# Arduino_8FSR.net
KiCad netlist of a schematic drawn in EAGLE
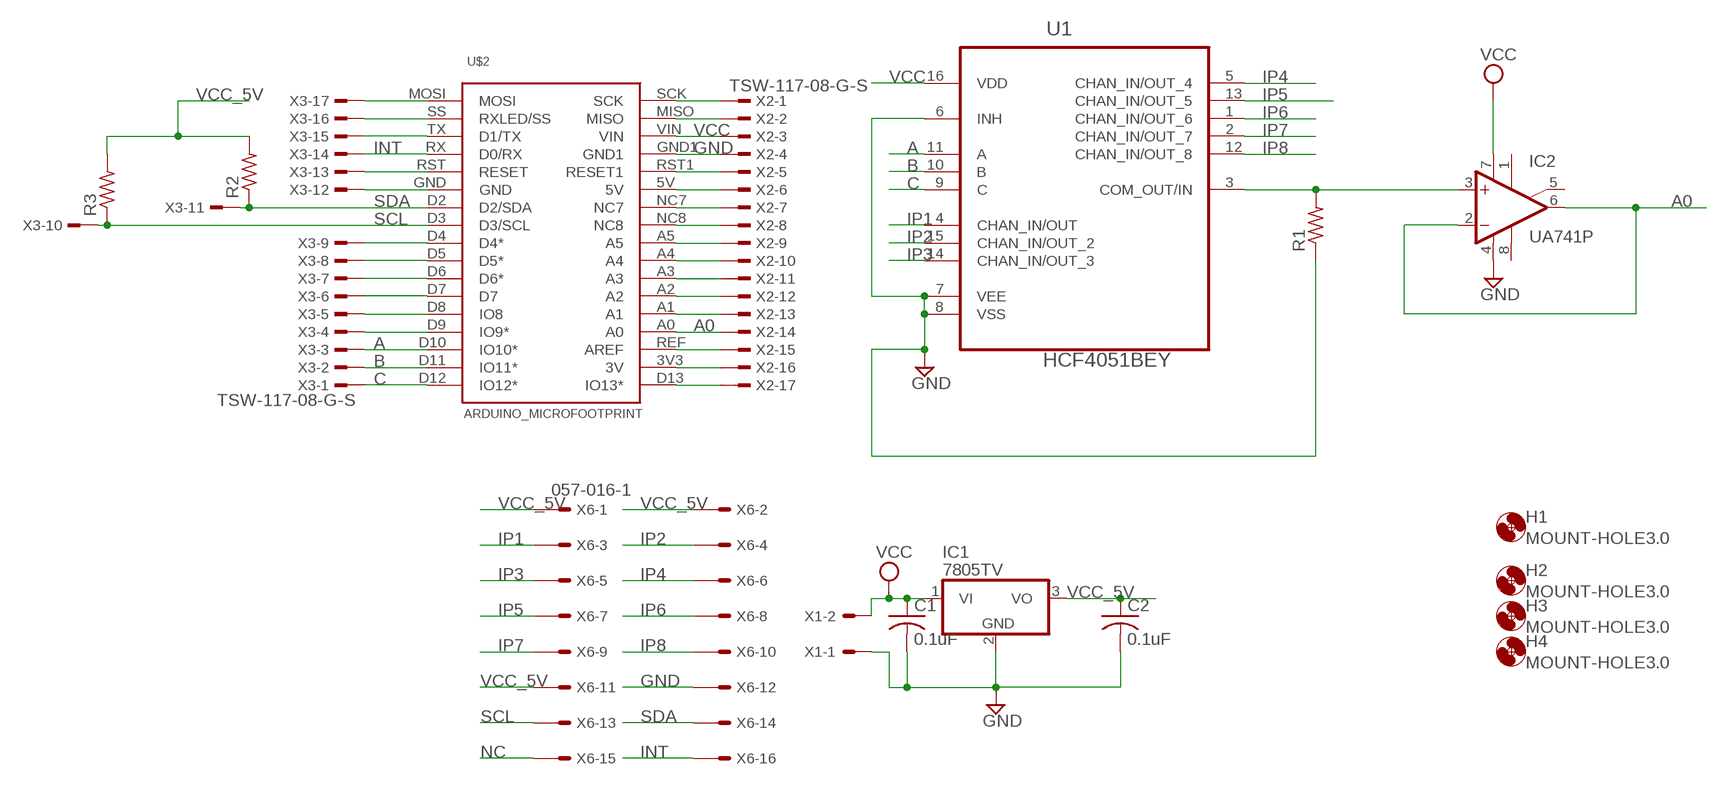
[diagram p0: schematic, sheet 1]

(export (version "E")
  (design (tool "Eeschema 10.0.6"))
  (components
    (comp (ref "C1")
      (value "0.1uF")
      (footprint "eagle-import:C025-024X044")
      (libsource (lib "eagle-import") (part "C-US025-024X044"))
    )
    (comp (ref "C2")
      (value "0.1uF")
      (footprint "eagle-import:C025-024X044")
      (libsource (lib "eagle-import") (part "C-US025-024X044"))
    )
    (comp (ref "H1")
      (value "MOUNT-HOLE3.0")
      (footprint "eagle-import:3,0")
      (libsource (lib "eagle-import") (part "MOUNT-HOLE3.0"))
    )
    (comp (ref "H2")
      (value "MOUNT-HOLE3.0")
      (footprint "eagle-import:3,0")
      (libsource (lib "eagle-import") (part "MOUNT-HOLE3.0"))
    )
    (comp (ref "H3")
      (value "MOUNT-HOLE3.0")
      (footprint "eagle-import:3,0")
      (libsource (lib "eagle-import") (part "MOUNT-HOLE3.0"))
    )
    (comp (ref "H4")
      (value "MOUNT-HOLE3.0")
      (footprint "eagle-import:3,0")
      (libsource (lib "eagle-import") (part "MOUNT-HOLE3.0"))
    )
    (comp (ref "IC1")
      (value "7805TV")
      (footprint "eagle-import:TO220V")
      (libsource (lib "eagle-import") (part "78TV05"))
    )
    (comp (ref "IC2")
      (value "UA741P")
      (footprint "eagle-import:DIL08")
      (libsource (lib "eagle-import") (part "741PUA"))
    )
    (comp (ref "R1")
      (value "R-US_0204/7")
      (footprint "eagle-import:0204_7")
      (libsource (lib "eagle-import") (part "R-US_0204/7"))
    )
    (comp (ref "R2")
      (value "R-US_0204/7")
      (footprint "eagle-import:0204_7")
      (libsource (lib "eagle-import") (part "R-US_0204/7"))
    )
    (comp (ref "R3")
      (value "R-US_0204/7")
      (footprint "eagle-import:0204_7")
      (libsource (lib "eagle-import") (part "R-US_0204/7"))
    )
    (comp (ref "U$2")
      (value "ARDUINO_MICROFOOTPRINT")
      (footprint "eagle-import:ARDUINO-MICRO")
      (libsource (lib "eagle-import") (part "ARDUINO_MICROFOOTPRINT"))
    )
    (comp (ref "U1")
      (value "HCF4051BEY")
      (footprint "eagle-import:DIP254P762X510-16")
      (fields (field (name "MF") "STMicroelectronics"))
      (libsource (lib "eagle-import") (part "HCF4051BEY"))
    )
    (comp (ref "X1")
      (value "KK-156-2")
      (footprint "eagle-import:KK-156-2")
      (fields (field (name "MF") "MOLEX"))
      (libsource (lib "eagle-import") (part "KK-156-2"))
    )
    (comp (ref "X2")
      (value "TSW-117-08-G-S")
      (footprint "eagle-import:TSW-117-XX-G-S")
      (fields (field (name "MF") "Samtec Inc.") (field (name "MPN") "TSW-117-07-G-S"))
      (libsource (lib "eagle-import") (part "TSW-117--G-S08"))
    )
    (comp (ref "X3")
      (value "TSW-117-08-G-S")
      (footprint "eagle-import:TSW-117-XX-G-S")
      (fields (field (name "MF") "Samtec Inc.") (field (name "MPN") "TSW-117-07-G-S"))
      (libsource (lib "eagle-import") (part "TSW-117--G-S08"))
    )
    (comp (ref "X6")
      (value "057-016-1")
      (footprint "eagle-import:057-016-1")
      (libsource (lib "eagle-import") (part "057-016-1"))
    )
  )
  (nets
    (net (code "1") (name "/A") (class "Default")
      (node (ref "U$2") (pin "D10") (pinfunction "IO10*_D10") (pintype "bidirectional"))
      (node (ref "U1") (pin "11") (pinfunction "A_11") (pintype "input"))
      (node (ref "X3") (pin "3") (pinfunction "1_3") (pintype "passive"))
    )
    (net (code "2") (name "/A0") (class "Default")
      (node (ref "IC2") (pin "2") (pinfunction "-IN_2") (pintype "input"))
      (node (ref "IC2") (pin "6") (pinfunction "OUT_6") (pintype "output"))
      (node (ref "U$2") (pin "A0") (pinfunction "A0_A0") (pintype "bidirectional"))
      (node (ref "X2") (pin "14") (pinfunction "1_14") (pintype "passive"))
    )
    (net (code "3") (name "/B") (class "Default")
      (node (ref "U$2") (pin "D11") (pinfunction "IO11*_D11") (pintype "bidirectional"))
      (node (ref "U1") (pin "10") (pinfunction "B_10") (pintype "input"))
      (node (ref "X3") (pin "2") (pinfunction "1_2") (pintype "passive"))
    )
    (net (code "4") (name "/C") (class "Default")
      (node (ref "U$2") (pin "D12") (pinfunction "IO12*_D12") (pintype "bidirectional"))
      (node (ref "U1") (pin "9") (pinfunction "C_9") (pintype "input"))
      (node (ref "X3") (pin "1") (pinfunction "1_1") (pintype "passive"))
    )
    (net (code "5") (name "/INT") (class "Default")
      (node (ref "U$2") (pin "RX") (pinfunction "D0/RX_RX") (pintype "bidirectional"))
      (node (ref "X3") (pin "14") (pinfunction "1_14") (pintype "passive"))
      (node (ref "X6") (pin "16") (pinfunction "S_16") (pintype "passive"))
    )
    (net (code "6") (name "/IP1") (class "Default")
      (node (ref "U1") (pin "4") (pinfunction "CHAN_IN/OUT_4") (pintype "bidirectional"))
      (node (ref "X6") (pin "3") (pinfunction "S_3") (pintype "passive"))
    )
    (net (code "7") (name "/IP2") (class "Default")
      (node (ref "U1") (pin "15") (pinfunction "CHAN_IN/OUT_2_15") (pintype "bidirectional"))
      (node (ref "X6") (pin "4") (pinfunction "S_4") (pintype "passive"))
    )
    (net (code "8") (name "/IP3") (class "Default")
      (node (ref "U1") (pin "14") (pinfunction "CHAN_IN/OUT_3_14") (pintype "bidirectional"))
      (node (ref "X6") (pin "5") (pinfunction "S_5") (pintype "passive"))
    )
    (net (code "9") (name "/IP4") (class "Default")
      (node (ref "U1") (pin "5") (pinfunction "CHAN_IN/OUT_4_5") (pintype "bidirectional"))
      (node (ref "X6") (pin "6") (pinfunction "S_6") (pintype "passive"))
    )
    (net (code "10") (name "/IP5") (class "Default")
      (node (ref "U1") (pin "13") (pinfunction "CHAN_IN/OUT_5_13") (pintype "bidirectional"))
      (node (ref "X6") (pin "7") (pinfunction "S_7") (pintype "passive"))
    )
    (net (code "11") (name "/IP6") (class "Default")
      (node (ref "U1") (pin "1") (pinfunction "CHAN_IN/OUT_6_1") (pintype "bidirectional"))
      (node (ref "X6") (pin "8") (pinfunction "S_8") (pintype "passive"))
    )
    (net (code "12") (name "/IP7") (class "Default")
      (node (ref "U1") (pin "2") (pinfunction "CHAN_IN/OUT_7_2") (pintype "bidirectional"))
      (node (ref "X6") (pin "9") (pinfunction "S_9") (pintype "passive"))
    )
    (net (code "13") (name "/IP8") (class "Default")
      (node (ref "U1") (pin "12") (pinfunction "CHAN_IN/OUT_8_12") (pintype "bidirectional"))
      (node (ref "X6") (pin "10") (pinfunction "S_10") (pintype "passive"))
    )
    (net (code "14") (name "/NC") (class "Default")
      (node (ref "X6") (pin "15") (pinfunction "S_15") (pintype "passive"))
    )
    (net (code "15") (name "/SCL") (class "Default")
      (node (ref "R3") (pin "1") (pinfunction "1_1") (pintype "passive"))
      (node (ref "U$2") (pin "D3") (pinfunction "D3/SCL_D3") (pintype "bidirectional"))
      (node (ref "X3") (pin "10") (pinfunction "1_10") (pintype "passive"))
      (node (ref "X6") (pin "13") (pinfunction "S_13") (pintype "passive"))
    )
    (net (code "16") (name "/SDA") (class "Default")
      (node (ref "R2") (pin "1") (pinfunction "1_1") (pintype "passive"))
      (node (ref "U$2") (pin "D2") (pinfunction "D2/SDA_D2") (pintype "bidirectional"))
      (node (ref "X3") (pin "11") (pinfunction "1_11") (pintype "passive"))
      (node (ref "X6") (pin "14") (pinfunction "S_14") (pintype "passive"))
    )
    (net (code "17") (name "/VCC_5V") (class "Default")
      (node (ref "C2") (pin "1") (pinfunction "1_1") (pintype "passive"))
      (node (ref "IC1") (pin "3") (pinfunction "VO_3") (pintype "passive"))
      (node (ref "R2") (pin "2") (pinfunction "2_2") (pintype "passive"))
      (node (ref "R3") (pin "2") (pinfunction "2_2") (pintype "passive"))
      (node (ref "X6") (pin "1") (pinfunction "S_1") (pintype "passive"))
      (node (ref "X6") (pin "11") (pinfunction "S_11") (pintype "passive"))
      (node (ref "X6") (pin "2") (pinfunction "S_2") (pintype "passive"))
    )
    (net (code "18") (name "GND") (class "Default")
      (node (ref "C1") (pin "2") (pinfunction "2_2") (pintype "passive"))
      (node (ref "C2") (pin "2") (pinfunction "2_2") (pintype "passive"))
      (node (ref "IC1") (pin "2") (pinfunction "GND_2") (pintype "passive"))
      (node (ref "IC2") (pin "4") (pinfunction "V-_4") (pintype "power_in"))
      (node (ref "R1") (pin "1") (pinfunction "1_1") (pintype "passive"))
      (node (ref "U$2") (pin "GND1") (pinfunction "GND1_GND1") (pintype "bidirectional"))
      (node (ref "U1") (pin "6") (pinfunction "INH_6") (pintype "passive"))
      (node (ref "U1") (pin "7") (pinfunction "VEE_7") (pintype "power_in"))
      (node (ref "U1") (pin "8") (pinfunction "VSS_8") (pintype "power_in"))
      (node (ref "X1") (pin "1") (pinfunction "S_1") (pintype "passive"))
      (node (ref "X2") (pin "4") (pinfunction "1_4") (pintype "passive"))
      (node (ref "X6") (pin "12") (pinfunction "S_12") (pintype "passive"))
    )
    (net (code "19") (name "Net-(IC2-+IN)") (class "Default")
      (node (ref "IC2") (pin "3") (pinfunction "+IN_3") (pintype "input"))
      (node (ref "R1") (pin "2") (pinfunction "2_2") (pintype "passive"))
      (node (ref "U1") (pin "3") (pinfunction "COM_OUT/IN_3") (pintype "bidirectional"))
    )
    (net (code "20") (name "Net-(U$2-3V)") (class "Default")
      (node (ref "U$2") (pin "3V3") (pinfunction "3V_3V3") (pintype "bidirectional"))
      (node (ref "X2") (pin "16") (pinfunction "1_16") (pintype "passive"))
    )
    (net (code "21") (name "Net-(U$2-AREF)") (class "Default")
      (node (ref "U$2") (pin "REF") (pinfunction "AREF_REF") (pintype "bidirectional"))
      (node (ref "X2") (pin "15") (pinfunction "1_15") (pintype "passive"))
    )
    (net (code "22") (name "Net-(U$2-D1{slash}TX)") (class "Default")
      (node (ref "U$2") (pin "TX") (pinfunction "D1/TX_TX") (pintype "bidirectional"))
      (node (ref "X3") (pin "15") (pinfunction "1_15") (pintype "passive"))
    )
    (net (code "23") (name "Net-(U$2-D4*)") (class "Default")
      (node (ref "U$2") (pin "D4") (pinfunction "D4*_D4") (pintype "bidirectional"))
      (node (ref "X3") (pin "9") (pinfunction "1_9") (pintype "passive"))
    )
    (net (code "24") (name "Net-(U$2-D5*)") (class "Default")
      (node (ref "U$2") (pin "D5") (pinfunction "D5*_D5") (pintype "bidirectional"))
      (node (ref "X3") (pin "8") (pinfunction "1_8") (pintype "passive"))
    )
    (net (code "25") (name "Net-(U$2-D6*)") (class "Default")
      (node (ref "U$2") (pin "D6") (pinfunction "D6*_D6") (pintype "bidirectional"))
      (node (ref "X3") (pin "7") (pinfunction "1_7") (pintype "passive"))
    )
    (net (code "26") (name "Net-(U$2-IO8)") (class "Default")
      (node (ref "U$2") (pin "D8") (pinfunction "IO8_D8") (pintype "bidirectional"))
      (node (ref "X3") (pin "5") (pinfunction "1_5") (pintype "passive"))
    )
    (net (code "27") (name "Net-(U$2-IO9*)") (class "Default")
      (node (ref "U$2") (pin "D9") (pinfunction "IO9*_D9") (pintype "bidirectional"))
      (node (ref "X3") (pin "4") (pinfunction "1_4") (pintype "passive"))
    )
    (net (code "28") (name "Net-(U$2-IO13*)") (class "Default")
      (node (ref "U$2") (pin "D13") (pinfunction "IO13*_D13") (pintype "bidirectional"))
      (node (ref "X2") (pin "17") (pinfunction "1_17") (pintype "passive"))
    )
    (net (code "29") (name "Net-(U$2-PadSCK)") (class "Default")
      (node (ref "U$2") (pin "SCK") (pinfunction "SCK_SCK") (pintype "bidirectional"))
      (node (ref "X2") (pin "1") (pinfunction "1_1") (pintype "passive"))
    )
    (net (code "30") (name "Net-(U$2-RESET)") (class "Default")
      (node (ref "U$2") (pin "RST") (pinfunction "RESET_RST") (pintype "bidirectional"))
      (node (ref "X3") (pin "13") (pinfunction "1_13") (pintype "passive"))
    )
    (net (code "31") (name "Net-(U$2-RESET1)") (class "Default")
      (node (ref "U$2") (pin "RST1") (pinfunction "RESET1_RST1") (pintype "bidirectional"))
      (node (ref "X2") (pin "5") (pinfunction "1_5") (pintype "passive"))
    )
    (net (code "32") (name "Net-(U$2-RXLED{slash}SS)") (class "Default")
      (node (ref "U$2") (pin "SS") (pinfunction "RXLED/SS_SS") (pintype "bidirectional"))
      (node (ref "X3") (pin "16") (pinfunction "1_16") (pintype "passive"))
    )
    (net (code "33") (name "Net-(X2B-1)") (class "Default")
      (node (ref "U$2") (pin "A4") (pinfunction "A4_A4") (pintype "bidirectional"))
      (node (ref "X2") (pin "10") (pinfunction "1_10") (pintype "passive"))
    )
    (net (code "34") (name "Net-(X2C-1)") (class "Default")
      (node (ref "U$2") (pin "A3") (pinfunction "A3_A3") (pintype "bidirectional"))
      (node (ref "X2") (pin "11") (pinfunction "1_11") (pintype "passive"))
    )
    (net (code "35") (name "Net-(X2D-1)") (class "Default")
      (node (ref "U$2") (pin "A2") (pinfunction "A2_A2") (pintype "bidirectional"))
      (node (ref "X2") (pin "12") (pinfunction "1_12") (pintype "passive"))
    )
    (net (code "36") (name "Net-(X2E-1)") (class "Default")
      (node (ref "U$2") (pin "A1") (pinfunction "A1_A1") (pintype "bidirectional"))
      (node (ref "X2") (pin "13") (pinfunction "1_13") (pintype "passive"))
    )
    (net (code "37") (name "Net-(X2J-1)") (class "Default")
      (node (ref "U$2") (pin "MISO") (pinfunction "MISO_MISO") (pintype "bidirectional"))
      (node (ref "X2") (pin "2") (pinfunction "1_2") (pintype "passive"))
    )
    (net (code "38") (name "Net-(X2N-1)") (class "Default")
      (node (ref "U$2") (pin "5V") (pinfunction "5V_5V") (pintype "bidirectional"))
      (node (ref "X2") (pin "6") (pinfunction "1_6") (pintype "passive"))
    )
    (net (code "39") (name "Net-(X2O-1)") (class "Default")
      (node (ref "U$2") (pin "NC7") (pinfunction "NC7_NC7") (pintype "bidirectional"))
      (node (ref "X2") (pin "7") (pinfunction "1_7") (pintype "passive"))
    )
    (net (code "40") (name "Net-(X2P-1)") (class "Default")
      (node (ref "U$2") (pin "NC8") (pinfunction "NC8_NC8") (pintype "bidirectional"))
      (node (ref "X2") (pin "8") (pinfunction "1_8") (pintype "passive"))
    )
    (net (code "41") (name "Net-(X2Q-1)") (class "Default")
      (node (ref "U$2") (pin "A5") (pinfunction "A5_A5") (pintype "bidirectional"))
      (node (ref "X2") (pin "9") (pinfunction "1_9") (pintype "passive"))
    )
    (net (code "42") (name "Net-(X3D-1)") (class "Default")
      (node (ref "U$2") (pin "GND") (pinfunction "GND_GND") (pintype "bidirectional"))
      (node (ref "X3") (pin "12") (pinfunction "1_12") (pintype "passive"))
    )
    (net (code "43") (name "Net-(X3I-1)") (class "Default")
      (node (ref "U$2") (pin "MOSI") (pinfunction "MOSI_MOSI") (pintype "bidirectional"))
      (node (ref "X3") (pin "17") (pinfunction "1_17") (pintype "passive"))
    )
    (net (code "44") (name "Net-(X3N-1)") (class "Default")
      (node (ref "U$2") (pin "D7") (pinfunction "D7_D7") (pintype "bidirectional"))
      (node (ref "X3") (pin "6") (pinfunction "1_6") (pintype "passive"))
    )
    (net (code "45") (name "VCC") (class "Default")
      (node (ref "C1") (pin "1") (pinfunction "1_1") (pintype "passive"))
      (node (ref "IC1") (pin "1") (pinfunction "VI_1") (pintype "input"))
      (node (ref "IC2") (pin "7") (pinfunction "V+_7") (pintype "power_in"))
      (node (ref "U$2") (pin "VIN") (pinfunction "VIN_VIN") (pintype "bidirectional"))
      (node (ref "U1") (pin "16") (pinfunction "VDD_16") (pintype "power_in"))
      (node (ref "X1") (pin "2") (pinfunction "S_2") (pintype "passive"))
      (node (ref "X2") (pin "3") (pinfunction "1_3") (pintype "passive"))
    )
    (net (code "46") (name "unconnected-(IC2-ON1-Pad1)") (class "Default")
      (node (ref "IC2") (pin "1") (pinfunction "ON1_1") (pintype "passive"))
    )
    (net (code "47") (name "unconnected-(IC2-ON2-Pad5)") (class "Default")
      (node (ref "IC2") (pin "5") (pinfunction "ON2_5") (pintype "passive"))
    )
    (net (code "48") (name "unconnected-(IC2-OPT-Pad8)") (class "Default")
      (node (ref "IC2") (pin "8") (pinfunction "OPT_8") (pintype "passive"))
    )
  )
)
